# untitled.net
KiCad netlist of a schematic drawn in EAGLE
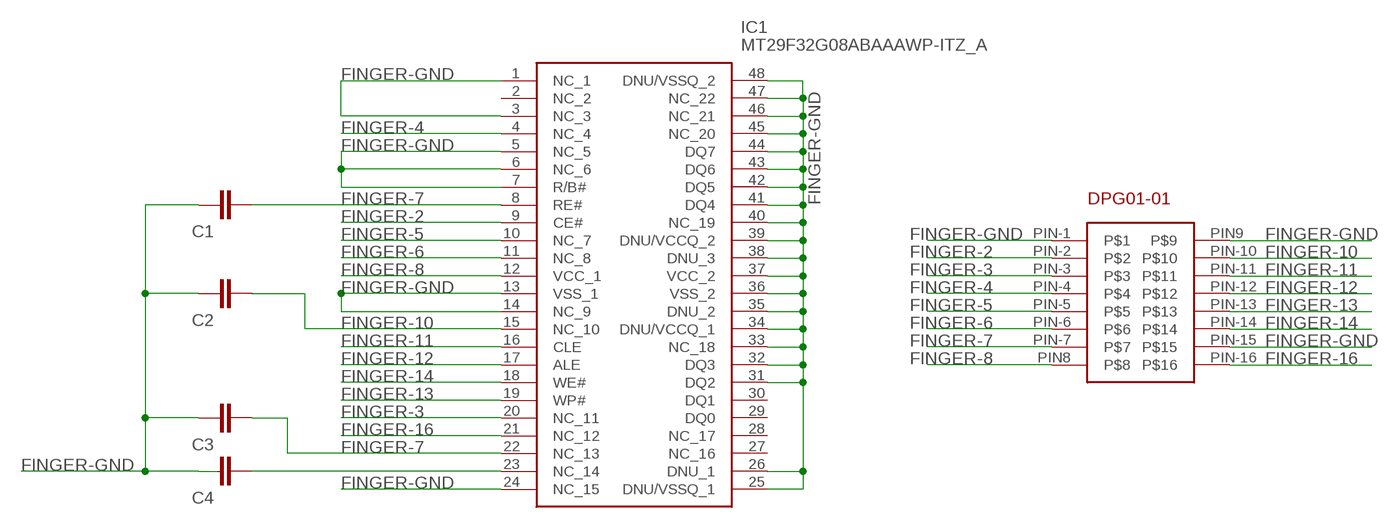
[diagram p0: schematic, sheet 1]

(export (version "E")
  (design (tool "Eeschema 10.0.6"))
  (components
    (comp (ref "C1")
      (value "C-EUC0402")
      (footprint "eagle-import:C0402")
      (libsource (lib "eagle-import") (part "C-EUC0402"))
    )
    (comp (ref "C2")
      (value "C-EUC0402")
      (footprint "eagle-import:C0402")
      (libsource (lib "eagle-import") (part "C-EUC0402"))
    )
    (comp (ref "C3")
      (value "C-EUC0402")
      (footprint "eagle-import:C0402")
      (libsource (lib "eagle-import") (part "C-EUC0402"))
    )
    (comp (ref "C4")
      (value "C-EUC0402")
      (footprint "eagle-import:C0402")
      (libsource (lib "eagle-import") (part "C-EUC0402"))
    )
    (comp (ref "IC1")
      (value "MT29F32G08ABAAAWP-ITZ_A")
      (footprint "eagle-import:SOP50P2000X120-48N")
      (fields
        (field (name "MANUFACTURER_PART_NUMBER") "MT29F32G08ABAAAWP-ITZ:A")
        (field (name "MOUSER_PART_NUMBER") "340-200226-TRAY")
      )
      (libsource (lib "eagle-import") (part "MT29F32G08ABAAAWP-ITZ_A"))
    )
    (comp (ref "U$1")
      (value "DPG01-01")
      (footprint "eagle-import:DPG01-01")
      (libsource (lib "eagle-import") (part "DPG01-01"))
    )
  )
  (nets
    (net (code "1") (name "/FINGER-2") (class "Default")
      (node (ref "IC1") (pin "9") (pinfunction "CE#_9") (pintype "bidirectional"))
      (node (ref "U$1") (pin "PIN-2") (pinfunction "P$2_PIN-2") (pintype "bidirectional"))
    )
    (net (code "2") (name "/FINGER-3") (class "Default")
      (node (ref "IC1") (pin "20") (pinfunction "NC_11_20") (pintype "bidirectional"))
      (node (ref "U$1") (pin "PIN-3") (pinfunction "P$3_PIN-3") (pintype "bidirectional"))
    )
    (net (code "3") (name "/FINGER-4") (class "Default")
      (node (ref "IC1") (pin "4") (pinfunction "NC_4_4") (pintype "bidirectional"))
      (node (ref "U$1") (pin "PIN-4") (pinfunction "P$4_PIN-4") (pintype "bidirectional"))
    )
    (net (code "4") (name "/FINGER-5") (class "Default")
      (node (ref "IC1") (pin "10") (pinfunction "NC_7_10") (pintype "bidirectional"))
      (node (ref "U$1") (pin "PIN-5") (pinfunction "P$5_PIN-5") (pintype "bidirectional"))
    )
    (net (code "5") (name "/FINGER-6") (class "Default")
      (node (ref "IC1") (pin "11") (pinfunction "NC_8_11") (pintype "bidirectional"))
      (node (ref "U$1") (pin "PIN-6") (pinfunction "P$6_PIN-6") (pintype "bidirectional"))
    )
    (net (code "6") (name "/FINGER-7") (class "Default")
      (node (ref "C1") (pin "1") (pinfunction "1_1") (pintype "passive"))
      (node (ref "C3") (pin "1") (pinfunction "1_1") (pintype "passive"))
      (node (ref "IC1") (pin "22") (pinfunction "NC_13_22") (pintype "bidirectional"))
      (node (ref "IC1") (pin "8") (pinfunction "RE#_8") (pintype "bidirectional"))
      (node (ref "U$1") (pin "PIN-7") (pinfunction "P$7_PIN-7") (pintype "bidirectional"))
    )
    (net (code "7") (name "/FINGER-8") (class "Default")
      (node (ref "IC1") (pin "12") (pinfunction "VCC_1_12") (pintype "bidirectional"))
      (node (ref "U$1") (pin "PIN8") (pinfunction "P$8_PIN8") (pintype "bidirectional"))
    )
    (net (code "8") (name "/FINGER-10") (class "Default")
      (node (ref "C2") (pin "1") (pinfunction "1_1") (pintype "passive"))
      (node (ref "IC1") (pin "15") (pinfunction "NC_10_15") (pintype "bidirectional"))
      (node (ref "U$1") (pin "PIN-10") (pinfunction "P$10_PIN-10") (pintype "bidirectional"))
    )
    (net (code "9") (name "/FINGER-11") (class "Default")
      (node (ref "IC1") (pin "16") (pinfunction "CLE_16") (pintype "bidirectional"))
      (node (ref "U$1") (pin "PIN-11") (pinfunction "P$11_PIN-11") (pintype "bidirectional"))
    )
    (net (code "10") (name "/FINGER-12") (class "Default")
      (node (ref "IC1") (pin "17") (pinfunction "ALE_17") (pintype "bidirectional"))
      (node (ref "U$1") (pin "PIN-12") (pinfunction "P$12_PIN-12") (pintype "bidirectional"))
    )
    (net (code "11") (name "/FINGER-13") (class "Default")
      (node (ref "IC1") (pin "19") (pinfunction "WP#_19") (pintype "bidirectional"))
      (node (ref "U$1") (pin "PIN-13") (pinfunction "P$13_PIN-13") (pintype "bidirectional"))
    )
    (net (code "12") (name "/FINGER-14") (class "Default")
      (node (ref "IC1") (pin "18") (pinfunction "WE#_18") (pintype "bidirectional"))
      (node (ref "U$1") (pin "PIN-14") (pinfunction "P$14_PIN-14") (pintype "bidirectional"))
    )
    (net (code "13") (name "/FINGER-16") (class "Default")
      (node (ref "IC1") (pin "21") (pinfunction "NC_12_21") (pintype "bidirectional"))
      (node (ref "U$1") (pin "PIN-16") (pinfunction "P$16_PIN-16") (pintype "bidirectional"))
    )
    (net (code "14") (name "/FINGER-GND") (class "Default")
      (node (ref "C1") (pin "2") (pinfunction "2_2") (pintype "passive"))
      (node (ref "C2") (pin "2") (pinfunction "2_2") (pintype "passive"))
      (node (ref "C3") (pin "2") (pinfunction "2_2") (pintype "passive"))
      (node (ref "C4") (pin "2") (pinfunction "2_2") (pintype "passive"))
      (node (ref "IC1") (pin "1") (pinfunction "NC_1_1") (pintype "bidirectional"))
      (node (ref "IC1") (pin "13") (pinfunction "VSS_1_13") (pintype "bidirectional"))
      (node (ref "IC1") (pin "14") (pinfunction "NC_9_14") (pintype "bidirectional"))
      (node (ref "IC1") (pin "24") (pinfunction "NC_15_24") (pintype "bidirectional"))
      (node (ref "IC1") (pin "25") (pinfunction "DNU/VSSQ_1_25") (pintype "bidirectional"))
      (node (ref "IC1") (pin "26") (pinfunction "DNU_1_26") (pintype "bidirectional"))
      (node (ref "IC1") (pin "3") (pinfunction "NC_3_3") (pintype "bidirectional"))
      (node (ref "IC1") (pin "31") (pinfunction "DQ2_31") (pintype "bidirectional"))
      (node (ref "IC1") (pin "32") (pinfunction "DQ3_32") (pintype "bidirectional"))
      (node (ref "IC1") (pin "33") (pinfunction "NC_18_33") (pintype "bidirectional"))
      (node (ref "IC1") (pin "34") (pinfunction "DNU/VCCQ_1_34") (pintype "bidirectional"))
      (node (ref "IC1") (pin "35") (pinfunction "DNU_2_35") (pintype "bidirectional"))
      (node (ref "IC1") (pin "36") (pinfunction "VSS_2_36") (pintype "bidirectional"))
      (node (ref "IC1") (pin "37") (pinfunction "VCC_2_37") (pintype "bidirectional"))
      (node (ref "IC1") (pin "38") (pinfunction "DNU_3_38") (pintype "bidirectional"))
      (node (ref "IC1") (pin "39") (pinfunction "DNU/VCCQ_2_39") (pintype "bidirectional"))
      (node (ref "IC1") (pin "40") (pinfunction "NC_19_40") (pintype "bidirectional"))
      (node (ref "IC1") (pin "41") (pinfunction "DQ4_41") (pintype "bidirectional"))
      (node (ref "IC1") (pin "42") (pinfunction "DQ5_42") (pintype "bidirectional"))
      (node (ref "IC1") (pin "43") (pinfunction "DQ6_43") (pintype "bidirectional"))
      (node (ref "IC1") (pin "44") (pinfunction "DQ7_44") (pintype "bidirectional"))
      (node (ref "IC1") (pin "45") (pinfunction "NC_20_45") (pintype "bidirectional"))
      (node (ref "IC1") (pin "46") (pinfunction "NC_21_46") (pintype "bidirectional"))
      (node (ref "IC1") (pin "47") (pinfunction "NC_22_47") (pintype "bidirectional"))
      (node (ref "IC1") (pin "48") (pinfunction "DNU/VSSQ_2_48") (pintype "bidirectional"))
      (node (ref "IC1") (pin "5") (pinfunction "NC_5_5") (pintype "bidirectional"))
      (node (ref "IC1") (pin "6") (pinfunction "NC_6_6") (pintype "bidirectional"))
      (node (ref "IC1") (pin "7") (pinfunction "R/B#_7") (pintype "bidirectional"))
      (node (ref "U$1") (pin "PIN-1") (pinfunction "P$1_PIN-1") (pintype "bidirectional"))
      (node (ref "U$1") (pin "PIN-15") (pinfunction "P$15_PIN-15") (pintype "bidirectional"))
      (node (ref "U$1") (pin "PIN9") (pinfunction "P$9_PIN9") (pintype "bidirectional"))
    )
    (net (code "15") (name "Net-(IC1-NC_14)") (class "Default")
      (node (ref "C4") (pin "1") (pinfunction "1_1") (pintype "passive"))
      (node (ref "IC1") (pin "23") (pinfunction "NC_14_23") (pintype "bidirectional"))
    )
    (net (code "16") (name "unconnected-(IC1-DQ0-Pad29)") (class "Default")
      (node (ref "IC1") (pin "29") (pinfunction "DQ0_29") (pintype "bidirectional"))
    )
    (net (code "17") (name "unconnected-(IC1-DQ1-Pad30)") (class "Default")
      (node (ref "IC1") (pin "30") (pinfunction "DQ1_30") (pintype "bidirectional"))
    )
    (net (code "18") (name "unconnected-(IC1-NC_2-Pad2)") (class "Default")
      (node (ref "IC1") (pin "2") (pinfunction "NC_2_2") (pintype "bidirectional"))
    )
    (net (code "19") (name "unconnected-(IC1-NC_16-Pad27)") (class "Default")
      (node (ref "IC1") (pin "27") (pinfunction "NC_16_27") (pintype "bidirectional"))
    )
    (net (code "20") (name "unconnected-(IC1-NC_17-Pad28)") (class "Default")
      (node (ref "IC1") (pin "28") (pinfunction "NC_17_28") (pintype "bidirectional"))
    )
  )
)
